# xambi_2_0.net
KiCad netlist of a schematic drawn in EAGLE
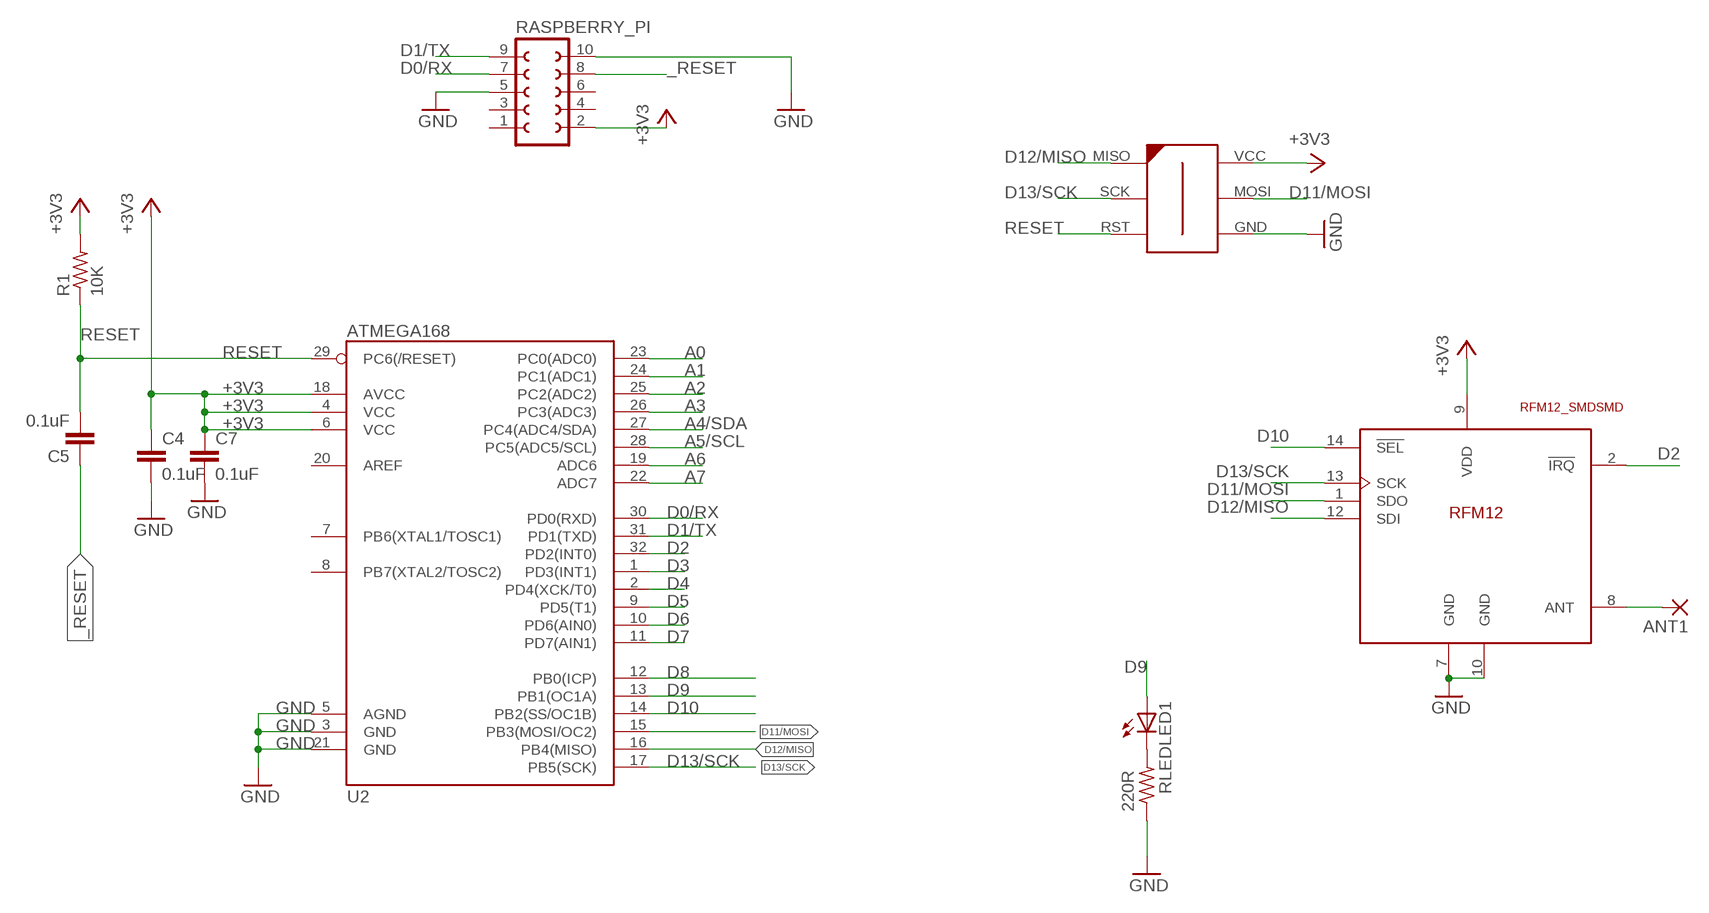
[diagram p0: schematic, sheet 1]

(export (version "E")
  (design (tool "Eeschema 10.0.6"))
  (components
    (comp (ref "ANT1")
      (value "1,6/0,8")
      (footprint "eagle-import:1,6_0,8")
      (libsource (lib "eagle-import") (part "1,6/0,8"))
    )
    (comp (ref "C4")
      (value "0.1uF")
      (footprint "eagle-import:C0603")
      (libsource (lib "eagle-import") (part "C-EUC0603"))
    )
    (comp (ref "C5")
      (value "0.1uF")
      (footprint "eagle-import:C0603")
      (libsource (lib "eagle-import") (part "C-EUC0603"))
    )
    (comp (ref "C7")
      (value "0.1uF")
      (footprint "eagle-import:C0603")
      (libsource (lib "eagle-import") (part "resistor_C-EUC0603"))
    )
    (comp (ref "ICSP")
      (value "AVR-ISP-6-EDGE")
      (footprint "eagle-import:6PAD_ISP")
      (libsource (lib "eagle-import") (part "AVR-ISP-6-EDGE"))
    )
    (comp (ref "LED1")
      (value "LEDSML0805")
      (footprint "eagle-import:SML0805")
      (libsource (lib "eagle-import") (part "LEDSML0805"))
    )
    (comp (ref "R1")
      (value "10K")
      (footprint "eagle-import:R0603")
      (libsource (lib "eagle-import") (part "R-US_R0603"))
    )
    (comp (ref "RASPBERRY_PI")
      (value "FE05-2")
      (footprint "eagle-import:FE05-2")
      (libsource (lib "eagle-import") (part "FE05-2"))
    )
    (comp (ref "RLED")
      (value "220R")
      (footprint "eagle-import:R0805")
      (libsource (lib "eagle-import") (part "R-US_R0805"))
    )
    (comp (ref "U$1")
      (value "RFM12_SMDSMD")
      (footprint "eagle-import:RFM12")
      (libsource (lib "eagle-import") (part "RFM12_SMDSMD"))
    )
    (comp (ref "U2")
      (value "ATMEGA168")
      (footprint "eagle-import:TQFP32-08")
      (libsource (lib "eagle-import") (part "ATMEGA168"))
    )
  )
  (nets
    (net (code "1") (name "+3V3") (class "Default")
      (node (ref "C4") (pin "1") (pinfunction "1_1") (pintype "passive"))
      (node (ref "C7") (pin "1") (pinfunction "1_1") (pintype "passive"))
      (node (ref "ICSP") (pin "VCC") (pinfunction "P$6_VCC") (pintype "bidirectional"))
      (node (ref "R1") (pin "2") (pinfunction "2_2") (pintype "passive"))
      (node (ref "RASPBERRY_PI") (pin "2") (pinfunction "2_2") (pintype "passive"))
      (node (ref "U$1") (pin "9") (pinfunction "VDD_9") (pintype "power_in"))
      (node (ref "U2") (pin "18") (pinfunction "AVCC_18") (pintype "bidirectional"))
      (node (ref "U2") (pin "4") (pinfunction "VCC_4") (pintype "bidirectional"))
      (node (ref "U2") (pin "6") (pinfunction "VCC_6") (pintype "bidirectional"))
    )
    (net (code "2") (name "/A0") (class "Default")
      (node (ref "U2") (pin "23") (pinfunction "PC0(ADC0)_23") (pintype "bidirectional"))
    )
    (net (code "3") (name "/A1") (class "Default")
      (node (ref "U2") (pin "24") (pinfunction "PC1(ADC1)_24") (pintype "bidirectional"))
    )
    (net (code "4") (name "/A2") (class "Default")
      (node (ref "U2") (pin "25") (pinfunction "PC2(ADC2)_25") (pintype "bidirectional"))
    )
    (net (code "5") (name "/A3") (class "Default")
      (node (ref "U2") (pin "26") (pinfunction "PC3(ADC3)_26") (pintype "bidirectional"))
    )
    (net (code "6") (name "/A4{slash}SDA") (class "Default")
      (node (ref "U2") (pin "27") (pinfunction "PC4(ADC4/SDA)_27") (pintype "bidirectional"))
    )
    (net (code "7") (name "/A5{slash}SCL") (class "Default")
      (node (ref "U2") (pin "28") (pinfunction "PC5(ADC5/SCL)_28") (pintype "bidirectional"))
    )
    (net (code "8") (name "/A6") (class "Default")
      (node (ref "U2") (pin "19") (pinfunction "ADC6_19") (pintype "bidirectional"))
    )
    (net (code "9") (name "/A7") (class "Default")
      (node (ref "U2") (pin "22") (pinfunction "ADC7_22") (pintype "bidirectional"))
    )
    (net (code "10") (name "/D0{slash}RX") (class "Default")
      (node (ref "RASPBERRY_PI") (pin "7") (pinfunction "7_7") (pintype "passive"))
      (node (ref "U2") (pin "30") (pinfunction "PD0(RXD)_30") (pintype "bidirectional"))
    )
    (net (code "11") (name "/D1{slash}TX") (class "Default")
      (node (ref "RASPBERRY_PI") (pin "9") (pinfunction "9_9") (pintype "passive"))
      (node (ref "U2") (pin "31") (pinfunction "PD1(TXD)_31") (pintype "bidirectional"))
    )
    (net (code "12") (name "/D2") (class "Default")
      (node (ref "U$1") (pin "2") (pinfunction "~{IRQ}_2") (pintype "output"))
      (node (ref "U2") (pin "32") (pinfunction "PD2(INT0)_32") (pintype "bidirectional"))
    )
    (net (code "13") (name "/D3") (class "Default")
      (node (ref "U2") (pin "1") (pinfunction "PD3(INT1)_1") (pintype "bidirectional"))
    )
    (net (code "14") (name "/D4") (class "Default")
      (node (ref "U2") (pin "2") (pinfunction "PD4(XCK/T0)_2") (pintype "bidirectional"))
    )
    (net (code "15") (name "/D5") (class "Default")
      (node (ref "U2") (pin "9") (pinfunction "PD5(T1)_9") (pintype "bidirectional"))
    )
    (net (code "16") (name "/D6") (class "Default")
      (node (ref "U2") (pin "10") (pinfunction "PD6(AIN0)_10") (pintype "bidirectional"))
    )
    (net (code "17") (name "/D7") (class "Default")
      (node (ref "U2") (pin "11") (pinfunction "PD7(AIN1)_11") (pintype "bidirectional"))
    )
    (net (code "18") (name "/D8") (class "Default")
      (node (ref "U2") (pin "12") (pinfunction "PB0(ICP)_12") (pintype "bidirectional"))
    )
    (net (code "19") (name "/D9") (class "Default")
      (node (ref "LED1") (pin "A") (pinfunction "A_A") (pintype "passive"))
      (node (ref "U2") (pin "13") (pinfunction "PB1(OC1A)_13") (pintype "bidirectional"))
    )
    (net (code "20") (name "/D10") (class "Default")
      (node (ref "U$1") (pin "14") (pinfunction "~{SEL}_14") (pintype "input"))
      (node (ref "U2") (pin "14") (pinfunction "PB2(SS/OC1B)_14") (pintype "bidirectional"))
    )
    (net (code "21") (name "/RESET") (class "Default")
      (node (ref "C5") (pin "2") (pinfunction "2_2") (pintype "passive"))
      (node (ref "ICSP") (pin "RST") (pinfunction "P$3_RST") (pintype "bidirectional"))
      (node (ref "R1") (pin "1") (pinfunction "1_1") (pintype "passive"))
      (node (ref "U2") (pin "29") (pinfunction "PC6(/RESET)_29") (pintype "bidirectional"))
    )
    (net (code "22") (name "D11{slash}MOSI") (class "Default")
      (node (ref "ICSP") (pin "MOSI") (pinfunction "P$5_MOSI") (pintype "bidirectional"))
      (node (ref "U$1") (pin "1") (pinfunction "SDO_1") (pintype "output"))
      (node (ref "U2") (pin "15") (pinfunction "PB3(MOSI/OC2)_15") (pintype "bidirectional"))
    )
    (net (code "23") (name "D12{slash}MISO") (class "Default")
      (node (ref "ICSP") (pin "MISO") (pinfunction "P$1_MISO") (pintype "bidirectional"))
      (node (ref "U$1") (pin "12") (pinfunction "SDI_12") (pintype "input"))
      (node (ref "U2") (pin "16") (pinfunction "PB4(MISO)_16") (pintype "bidirectional"))
    )
    (net (code "24") (name "D13{slash}SCK") (class "Default")
      (node (ref "ICSP") (pin "SCK") (pinfunction "P$2_SCK") (pintype "bidirectional"))
      (node (ref "U$1") (pin "13") (pinfunction "SCK_13") (pintype "input"))
      (node (ref "U2") (pin "17") (pinfunction "PB5(SCK)_17") (pintype "bidirectional"))
    )
    (net (code "25") (name "GND") (class "Default")
      (node (ref "C4") (pin "2") (pinfunction "2_2") (pintype "passive"))
      (node (ref "C7") (pin "2") (pinfunction "2_2") (pintype "passive"))
      (node (ref "ICSP") (pin "GND") (pinfunction "P$4_GND") (pintype "bidirectional"))
      (node (ref "RASPBERRY_PI") (pin "10") (pinfunction "10_10") (pintype "passive"))
      (node (ref "RASPBERRY_PI") (pin "5") (pinfunction "5_5") (pintype "passive"))
      (node (ref "RLED") (pin "1") (pinfunction "1_1") (pintype "passive"))
      (node (ref "U$1") (pin "10") (pinfunction "GND_10") (pintype "passive"))
      (node (ref "U$1") (pin "7") (pinfunction "GND_7") (pintype "passive"))
      (node (ref "U2") (pin "21") (pinfunction "GND_21") (pintype "bidirectional"))
      (node (ref "U2") (pin "3") (pinfunction "GND_3") (pintype "bidirectional"))
      (node (ref "U2") (pin "5") (pinfunction "AGND_5") (pintype "bidirectional"))
    )
    (net (code "26") (name "Net-(ANT1-P)") (class "Default")
      (node (ref "ANT1") (pin "1") (pinfunction "P_1") (pintype "passive"))
      (node (ref "U$1") (pin "8") (pinfunction "ANT_8") (pintype "bidirectional"))
    )
    (net (code "27") (name "Net-(LED1-PadC)") (class "Default")
      (node (ref "LED1") (pin "C") (pinfunction "C_C") (pintype "passive"))
      (node (ref "RLED") (pin "2") (pinfunction "2_2") (pintype "passive"))
    )
    (net (code "28") (name "_RESET") (class "Default")
      (node (ref "C5") (pin "1") (pinfunction "1_1") (pintype "passive"))
      (node (ref "RASPBERRY_PI") (pin "8") (pinfunction "8_8") (pintype "passive"))
    )
    (net (code "29") (name "unconnected-(RASPBERRY_PI-Pad1)") (class "Default")
      (node (ref "RASPBERRY_PI") (pin "1") (pinfunction "1_1") (pintype "passive"))
    )
    (net (code "30") (name "unconnected-(RASPBERRY_PI-Pad3)") (class "Default")
      (node (ref "RASPBERRY_PI") (pin "3") (pinfunction "3_3") (pintype "passive"))
    )
    (net (code "31") (name "unconnected-(RASPBERRY_PI-Pad4)") (class "Default")
      (node (ref "RASPBERRY_PI") (pin "4") (pinfunction "4_4") (pintype "passive"))
    )
    (net (code "32") (name "unconnected-(RASPBERRY_PI-Pad6)") (class "Default")
      (node (ref "RASPBERRY_PI") (pin "6") (pinfunction "6_6") (pintype "passive"))
    )
    (net (code "33") (name "unconnected-(U2-AREF-Pad20)") (class "Default")
      (node (ref "U2") (pin "20") (pinfunction "AREF_20") (pintype "bidirectional"))
    )
    (net (code "34") (name "unconnected-(U2-PB6(XTAL1{slash}TOSC1)-Pad7)") (class "Default")
      (node (ref "U2") (pin "7") (pinfunction "PB6(XTAL1/TOSC1)_7") (pintype "bidirectional"))
    )
    (net (code "35") (name "unconnected-(U2-PB7(XTAL2{slash}TOSC2)-Pad8)") (class "Default")
      (node (ref "U2") (pin "8") (pinfunction "PB7(XTAL2/TOSC2)_8") (pintype "bidirectional"))
    )
  )
)
